# 04_OSD.net
KiCad netlist of a schematic drawn in Altium Designer
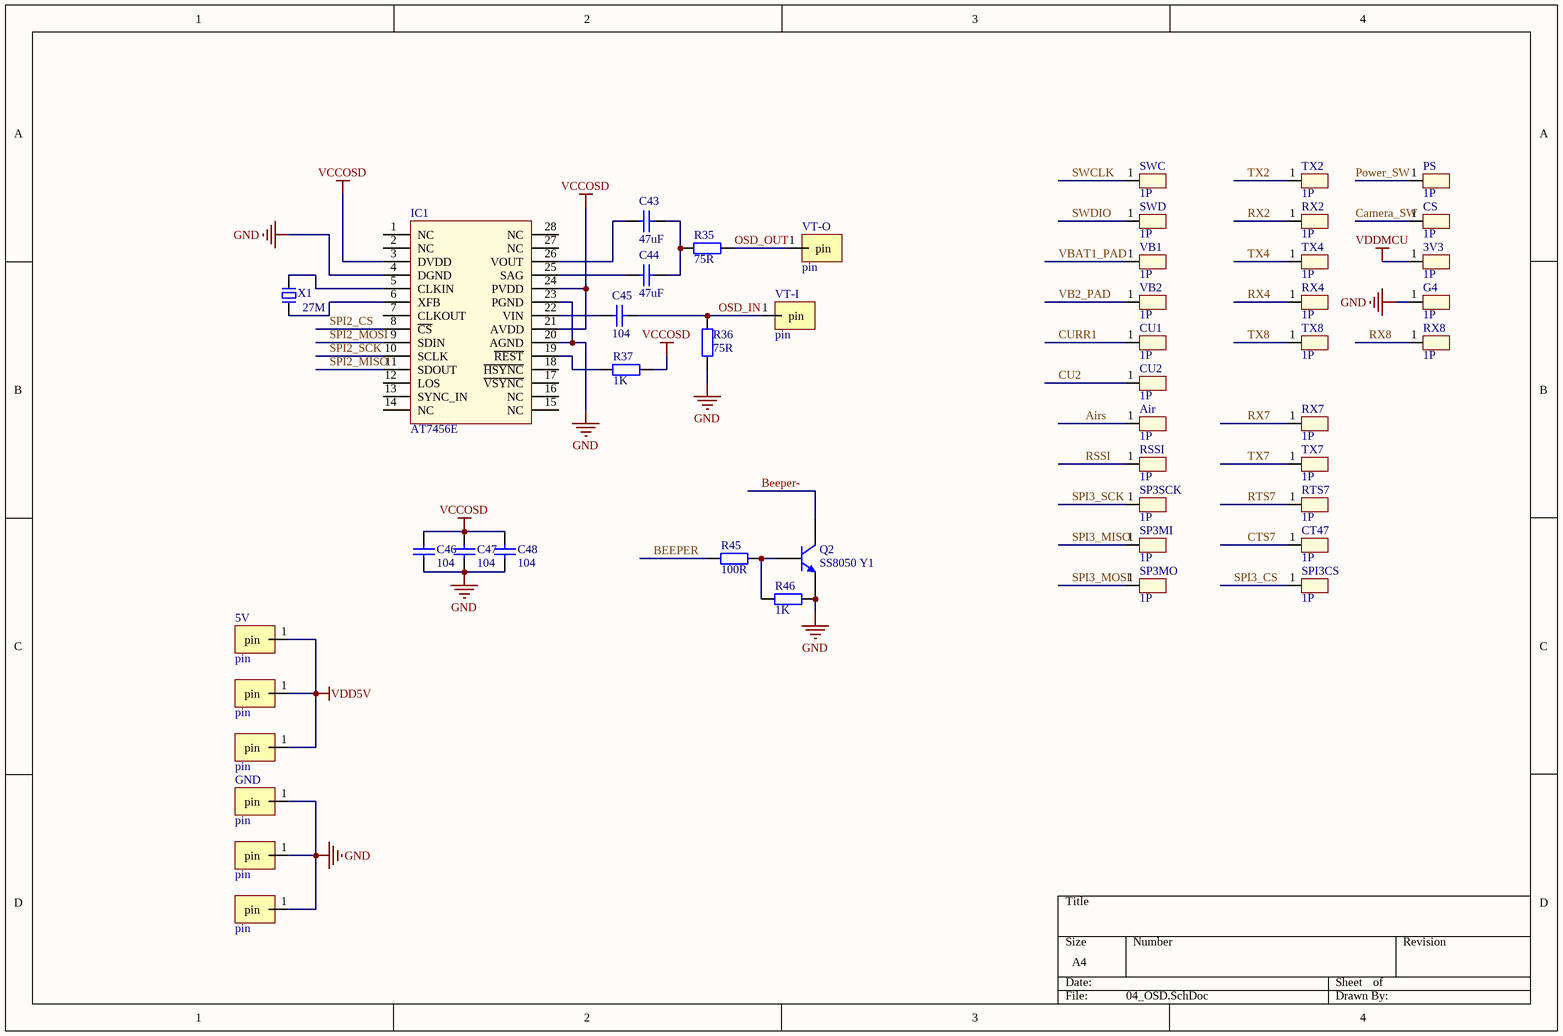
[diagram p0: 04_OSD.SchDoc]

(export (version "E")
  (design (tool "Eeschema 10.0.6"))
  (components
    (comp (ref "3V3") (value "1P") (footprint "1P-1.0") (libsource (lib "My_schlib") (part "1P")))
    (comp (ref "5V") (value "pin") (footprint "DIAN_0.5-1.0") (libsource (lib "") (part "dian_1")))
    (comp (ref "5V1") (value "pin") (footprint "DIAN_0.5-1.0") (libsource (lib "") (part "dian_1")))
    (comp (ref "5V2") (value "pin") (footprint "DIAN_0.5-1.0") (libsource (lib "") (part "dian_1")))
    (comp (ref "Air") (value "1P") (footprint "1P-1.0") (libsource (lib "My_schlib") (part "1P")))
    (comp (ref "C43")
      (value "47uF")
      (footprint "0805_C")
      (description "贴片电容")
      (libsource (lib "Miscellaneous Devices LC") (part "0805 100nF(104) 10% 50V"))
    )
    (comp (ref "C44")
      (value "47uF")
      (footprint "0805_C")
      (description "贴片电容")
      (libsource (lib "Miscellaneous Devices LC") (part "0805 100nF(104) 10% 50V"))
    )
    (comp (ref "C45")
      (value "104")
      (footprint "0402_C")
      (description "贴片电容")
      (libsource (lib "Miscellaneous Devices LC") (part "0402 100nF (104) 10% 16V"))
    )
    (comp (ref "C46")
      (value "104")
      (footprint "0402_C")
      (description "贴片电容")
      (libsource (lib "Miscellaneous Devices LC") (part "0402 100nF (104) 10% 16V"))
    )
    (comp (ref "C47")
      (value "104")
      (footprint "0402_C")
      (description "贴片电容")
      (libsource (lib "Miscellaneous Devices LC") (part "0402 100nF (104) 10% 16V"))
    )
    (comp (ref "C48")
      (value "104")
      (footprint "0402_C")
      (description "贴片电容")
      (libsource (lib "Miscellaneous Devices LC") (part "0402 100nF (104) 10% 16V"))
    )
    (comp (ref "CS") (value "1P") (footprint "1P-1.0") (libsource (lib "My_schlib") (part "1P")))
    (comp (ref "CT47") (value "1P") (footprint "1P-1.0") (libsource (lib "My_schlib") (part "1P")))
    (comp (ref "CU1") (value "1P") (footprint "1P-1.0") (libsource (lib "My_schlib") (part "1P")))
    (comp (ref "CU2") (value "1P") (footprint "1P-1.0") (libsource (lib "My_schlib") (part "1P")))
    (comp (ref "G2") (value "pin") (footprint "DIAN_0.5-1.0") (libsource (lib "") (part "dian_1")))
    (comp (ref "G3") (value "pin") (footprint "DIAN_0.5-1.0") (libsource (lib "") (part "dian_1")))
    (comp (ref "G4") (value "1P") (footprint "1P-1.0") (libsource (lib "My_schlib") (part "1P")))
    (comp (ref "GND") (value "pin") (footprint "DIAN_0.5-1.0") (libsource (lib "") (part "dian_1")))
    (comp (ref "IC1")
      (value "AT7456E")
      (footprint "TSSOP28_L_E")
      (description "OSD芯片")
      (libsource (lib "My_schlib") (part "AT7456E"))
    )
    (comp (ref "PS") (value "1P") (footprint "1P-1.0") (libsource (lib "My_schlib") (part "1P")))
    (comp (ref "Q2")
      (value "SS8050 Y1")
      (footprint "SOT-23(SOT-23-3)")
      (description "三极管")
      (libsource (lib "Miscellaneous Devices LC") (part "SOT-23 SS8050 Y1"))
    )
    (comp (ref "R35")
      (value "75R")
      (footprint "0402_R")
      (description "贴片电阻")
      (libsource (lib "Miscellaneous Devices LC") (part "0402 100Ω (1000) 1%"))
    )
    (comp (ref "R36")
      (value "75R")
      (footprint "0402_R")
      (description "贴片电阻")
      (libsource (lib "") (part "0402 100Ω (1000) 1%_1"))
    )
    (comp (ref "R37")
      (value "1K")
      (footprint "0402_R")
      (description "贴片电阻")
      (libsource (lib "Miscellaneous Devices LC") (part "0402 100Ω (1000) 1%"))
    )
    (comp (ref "R45")
      (value "100R")
      (footprint "0402_R")
      (description "贴片电阻")
      (libsource (lib "Miscellaneous Devices LC") (part "0402 100Ω (1000) 1%"))
    )
    (comp (ref "R46")
      (value "1K")
      (footprint "0402_R")
      (description "贴片电阻")
      (libsource (lib "Miscellaneous Devices LC") (part "0402 100Ω (1000) 1%"))
    )
    (comp (ref "RSSI") (value "1P") (footprint "1P-1.0") (libsource (lib "My_schlib") (part "1P")))
    (comp (ref "RTS7") (value "1P") (footprint "1P-1.0") (libsource (lib "My_schlib") (part "1P")))
    (comp (ref "RX2") (value "1P") (footprint "1P-1.0") (libsource (lib "My_schlib") (part "1P")))
    (comp (ref "RX4") (value "1P") (footprint "1P-1.0") (libsource (lib "My_schlib") (part "1P")))
    (comp (ref "RX7") (value "1P") (footprint "1P-1.0") (libsource (lib "My_schlib") (part "1P")))
    (comp (ref "RX8") (value "1P") (footprint "1P-1.0") (libsource (lib "My_schlib") (part "1P")))
    (comp (ref "SP3MI") (value "1P") (footprint "1P-1.0") (libsource (lib "My_schlib") (part "1P")))
    (comp (ref "SP3MO") (value "1P") (footprint "1P-1.0") (libsource (lib "My_schlib") (part "1P")))
    (comp (ref "SP3SCK") (value "1P") (footprint "1P-1.0") (libsource (lib "My_schlib") (part "1P")))
    (comp (ref "SPI3CS") (value "1P") (footprint "1P-1.0") (libsource (lib "My_schlib") (part "1P")))
    (comp (ref "SWC") (value "1P") (footprint "1P-1.0") (libsource (lib "My_schlib") (part "1P")))
    (comp (ref "SWD") (value "1P") (footprint "1P-1.0") (libsource (lib "My_schlib") (part "1P")))
    (comp (ref "TX2") (value "1P") (footprint "1P-1.0") (libsource (lib "My_schlib") (part "1P")))
    (comp (ref "TX4") (value "1P") (footprint "1P-1.0") (libsource (lib "My_schlib") (part "1P")))
    (comp (ref "TX7") (value "1P") (footprint "1P-1.0") (libsource (lib "My_schlib") (part "1P")))
    (comp (ref "TX8") (value "1P") (footprint "1P-1.0") (libsource (lib "My_schlib") (part "1P")))
    (comp (ref "VB1") (value "1P") (footprint "1P-1.0") (libsource (lib "My_schlib") (part "1P")))
    (comp (ref "VB2") (value "1P") (footprint "1P-1.0") (libsource (lib "My_schlib") (part "1P")))
    (comp (ref "VT-I") (value "pin") (footprint "DIAN_0.5-1.0") (libsource (lib "My_schlib") (part "dian")))
    (comp (ref "VT-O") (value "pin") (footprint "DIAN_0.5-1.0") (libsource (lib "My_schlib") (part "dian")))
    (comp (ref "X1")
      (value "27M")
      (footprint "XTAL-3225")
      (description "4脚无源晶振")
      (fields (field (name "版权归属") "源创客"))
      (libsource (lib "My_schlib") (part "XTAL-4P"))
    )
  )
  (nets
    (net (code "1") (name "/Airs") (class "Default") (node (ref "Air") (pin "1") (pintype "passive")))
    (net (code "2") (name "/BEEPER") (class "Default")
      (node (ref "R45") (pin "1") (pinfunction "1_1") (pintype "passive"))
    )
    (net (code "3") (name "/Beeper-") (class "Default")
      (node (ref "Q2") (pin "3") (pinfunction "C_3") (pintype "passive"))
    )
    (net (code "4") (name "/CTS7") (class "Default") (node (ref "CT47") (pin "1") (pintype "passive")))
    (net (code "5") (name "/CU2") (class "Default") (node (ref "CU2") (pin "1") (pintype "passive")))
    (net (code "6") (name "/CURR1") (class "Default") (node (ref "CU1") (pin "1") (pintype "passive")))
    (net (code "7") (name "/Camera_SW") (class "Default") (node (ref "CS") (pin "1") (pintype "passive")))
    (net (code "8") (name "/OSD_IN") (class "Default")
      (node (ref "C45") (pin "2") (pinfunction "2_2") (pintype "passive"))
      (node (ref "R36") (pin "2") (pinfunction "2_2") (pintype "passive"))
      (node (ref "VT-I") (pin "1") (pinfunction "pin_1") (pintype "passive"))
    )
    (net (code "9") (name "/OSD_OUT") (class "Default")
      (node (ref "R35") (pin "2") (pinfunction "2_2") (pintype "passive"))
      (node (ref "VT-O") (pin "1") (pinfunction "pin_1") (pintype "passive"))
    )
    (net (code "10") (name "/Power_SW") (class "Default") (node (ref "PS") (pin "1") (pintype "passive")))
    (net (code "11") (name "/RSSI") (class "Default") (node (ref "RSSI") (pin "1") (pintype "passive")))
    (net (code "12") (name "/RTS7") (class "Default") (node (ref "RTS7") (pin "1") (pintype "passive")))
    (net (code "13") (name "/RX2") (class "Default") (node (ref "RX2") (pin "1") (pintype "passive")))
    (net (code "14") (name "/RX4") (class "Default") (node (ref "RX4") (pin "1") (pintype "passive")))
    (net (code "15") (name "/RX7") (class "Default") (node (ref "RX7") (pin "1") (pintype "passive")))
    (net (code "16") (name "/RX8") (class "Default") (node (ref "RX8") (pin "1") (pintype "passive")))
    (net (code "17") (name "/SPI2_CS") (class "Default")
      (node (ref "IC1") (pin "8") (pinfunction "~{CS}_8") (pintype "passive"))
    )
    (net (code "18") (name "/SPI2_MISO") (class "Default")
      (node (ref "IC1") (pin "11") (pinfunction "SDOUT_11") (pintype "passive"))
    )
    (net (code "19") (name "/SPI2_MOSI") (class "Default")
      (node (ref "IC1") (pin "9") (pinfunction "SDIN_9") (pintype "passive"))
    )
    (net (code "20") (name "/SPI2_SCK") (class "Default")
      (node (ref "IC1") (pin "10") (pinfunction "SCLK_10") (pintype "passive"))
    )
    (net (code "21") (name "/SPI3_CS") (class "Default") (node (ref "SPI3CS") (pin "1") (pintype "passive")))
    (net (code "22") (name "/SPI3_MISO") (class "Default") (node (ref "SP3MI") (pin "1") (pintype "passive")))
    (net (code "23") (name "/SPI3_MOSI") (class "Default") (node (ref "SP3MO") (pin "1") (pintype "passive")))
    (net (code "24") (name "/SPI3_SCK") (class "Default") (node (ref "SP3SCK") (pin "1") (pintype "passive")))
    (net (code "25") (name "/SWCLK") (class "Default") (node (ref "SWC") (pin "1") (pintype "passive")))
    (net (code "26") (name "/SWDIO") (class "Default") (node (ref "SWD") (pin "1") (pintype "passive")))
    (net (code "27") (name "/TX2") (class "Default") (node (ref "TX2") (pin "1") (pintype "passive")))
    (net (code "28") (name "/TX4") (class "Default") (node (ref "TX4") (pin "1") (pintype "passive")))
    (net (code "29") (name "/TX7") (class "Default") (node (ref "TX7") (pin "1") (pintype "passive")))
    (net (code "30") (name "/TX8") (class "Default") (node (ref "TX8") (pin "1") (pintype "passive")))
    (net (code "31") (name "/VB2_PAD") (class "Default") (node (ref "VB2") (pin "1") (pintype "passive")))
    (net (code "32") (name "/VBAT1_PAD") (class "Default") (node (ref "VB1") (pin "1") (pintype "passive")))
    (net (code "33") (name "GND") (class "Default")
      (node (ref "C46") (pin "2") (pinfunction "2_2") (pintype "passive"))
      (node (ref "C47") (pin "2") (pinfunction "2_2") (pintype "passive"))
      (node (ref "C48") (pin "2") (pinfunction "2_2") (pintype "passive"))
      (node (ref "G2") (pin "1") (pinfunction "pin_1") (pintype "passive"))
      (node (ref "G3") (pin "1") (pinfunction "pin_1") (pintype "passive"))
      (node (ref "G4") (pin "1") (pintype "passive"))
      (node (ref "GND") (pin "1") (pinfunction "pin_1") (pintype "passive"))
      (node (ref "IC1") (pin "20") (pinfunction "AGND_20") (pintype "passive"))
      (node (ref "IC1") (pin "23") (pinfunction "PGND_23") (pintype "passive"))
      (node (ref "IC1") (pin "4") (pinfunction "DGND_4") (pintype "passive"))
      (node (ref "Q2") (pin "2") (pinfunction "E_2") (pintype "passive"))
      (node (ref "R36") (pin "1") (pinfunction "1_1") (pintype "passive"))
      (node (ref "R46") (pin "2") (pinfunction "2_2") (pintype "passive"))
    )
    (net (code "34") (name "Net-(C43-Pad2)") (class "Default")
      (node (ref "C43") (pin "2") (pinfunction "2_2") (pintype "passive"))
      (node (ref "C44") (pin "2") (pinfunction "2_2") (pintype "passive"))
      (node (ref "R35") (pin "1") (pinfunction "1_1") (pintype "passive"))
    )
    (net (code "35") (name "Net-(IC1-CLKIN)") (class "Default")
      (node (ref "IC1") (pin "5") (pinfunction "CLKIN_5") (pintype "passive"))
      (node (ref "X1") (pin "3") (pinfunction "3_3") (pintype "passive"))
    )
    (net (code "36") (name "Net-(IC1-SAG)") (class "Default")
      (node (ref "C44") (pin "1") (pinfunction "1_1") (pintype "passive"))
      (node (ref "IC1") (pin "25") (pinfunction "SAG_25") (pintype "passive"))
    )
    (net (code "37") (name "Net-(IC1-VIN)") (class "Default")
      (node (ref "C45") (pin "1") (pinfunction "1_1") (pintype "passive"))
      (node (ref "IC1") (pin "22") (pinfunction "VIN_22") (pintype "passive"))
    )
    (net (code "38") (name "Net-(IC1-VOUT)") (class "Default")
      (node (ref "C43") (pin "1") (pinfunction "1_1") (pintype "passive"))
      (node (ref "IC1") (pin "26") (pinfunction "VOUT_26") (pintype "passive"))
    )
    (net (code "39") (name "Net-(IC1-XFB)") (class "Default")
      (node (ref "IC1") (pin "6") (pinfunction "XFB_6") (pintype "passive"))
      (node (ref "X1") (pin "1") (pinfunction "1_1") (pintype "passive"))
    )
    (net (code "40") (name "Net-(IC1-~{REST})") (class "Default")
      (node (ref "IC1") (pin "19") (pinfunction "~{REST}_19") (pintype "passive"))
      (node (ref "R37") (pin "1") (pinfunction "1_1") (pintype "passive"))
    )
    (net (code "41") (name "Net-(Q2-B)") (class "Default")
      (node (ref "Q2") (pin "1") (pinfunction "B_1") (pintype "passive"))
      (node (ref "R45") (pin "2") (pinfunction "2_2") (pintype "passive"))
      (node (ref "R46") (pin "1") (pinfunction "1_1") (pintype "passive"))
    )
    (net (code "42") (name "VCCOSD") (class "Default")
      (node (ref "C46") (pin "1") (pinfunction "1_1") (pintype "passive"))
      (node (ref "C47") (pin "1") (pinfunction "1_1") (pintype "passive"))
      (node (ref "C48") (pin "1") (pinfunction "1_1") (pintype "passive"))
      (node (ref "IC1") (pin "21") (pinfunction "AVDD_21") (pintype "passive"))
      (node (ref "IC1") (pin "24") (pinfunction "PVDD_24") (pintype "passive"))
      (node (ref "IC1") (pin "3") (pinfunction "DVDD_3") (pintype "passive"))
      (node (ref "R37") (pin "2") (pinfunction "2_2") (pintype "passive"))
    )
    (net (code "43") (name "VDD5V") (class "Default")
      (node (ref "5V") (pin "1") (pinfunction "pin_1") (pintype "passive"))
      (node (ref "5V1") (pin "1") (pinfunction "pin_1") (pintype "passive"))
      (node (ref "5V2") (pin "1") (pinfunction "pin_1") (pintype "passive"))
    )
    (net (code "44") (name "VDDMCU") (class "Default") (node (ref "3V3") (pin "1") (pintype "passive")))
    (net (code "45") (name "unconnected-(IC1-CLKOUT-Pad7)") (class "Default")
      (node (ref "IC1") (pin "7") (pinfunction "CLKOUT_7") (pintype "passive"))
    )
    (net (code "46") (name "unconnected-(IC1-LOS-Pad12)") (class "Default")
      (node (ref "IC1") (pin "12") (pinfunction "LOS_12") (pintype "passive"))
    )
    (net (code "47") (name "unconnected-(IC1-NC-Pad1)") (class "Default")
      (node (ref "IC1") (pin "1") (pinfunction "NC_1") (pintype "passive"))
    )
    (net (code "48") (name "unconnected-(IC1-NC-Pad2)") (class "Default")
      (node (ref "IC1") (pin "2") (pinfunction "NC_2") (pintype "passive"))
    )
    (net (code "49") (name "unconnected-(IC1-NC-Pad14)") (class "Default")
      (node (ref "IC1") (pin "14") (pinfunction "NC_14") (pintype "passive"))
    )
    (net (code "50") (name "unconnected-(IC1-NC-Pad15)") (class "Default")
      (node (ref "IC1") (pin "15") (pinfunction "NC_15") (pintype "passive"))
    )
    (net (code "51") (name "unconnected-(IC1-NC-Pad16)") (class "Default")
      (node (ref "IC1") (pin "16") (pinfunction "NC_16") (pintype "passive"))
    )
    (net (code "52") (name "unconnected-(IC1-NC-Pad27)") (class "Default")
      (node (ref "IC1") (pin "27") (pinfunction "NC_27") (pintype "passive"))
    )
    (net (code "53") (name "unconnected-(IC1-NC-Pad28)") (class "Default")
      (node (ref "IC1") (pin "28") (pinfunction "NC_28") (pintype "passive"))
    )
    (net (code "54") (name "unconnected-(IC1-SYNC_IN-Pad13)") (class "Default")
      (node (ref "IC1") (pin "13") (pinfunction "SYNC_IN_13") (pintype "passive"))
    )
    (net (code "55") (name "unconnected-(IC1-~{HSYNC}-Pad18)") (class "Default")
      (node (ref "IC1") (pin "18") (pinfunction "~{HSYNC}_18") (pintype "passive"))
    )
    (net (code "56") (name "unconnected-(IC1-~{VSYNC}-Pad17)") (class "Default")
      (node (ref "IC1") (pin "17") (pinfunction "~{VSYNC}_17") (pintype "passive"))
    )
  )
)
